# Gripper_Control_Board.net
KiCad netlist of a schematic drawn in EAGLE
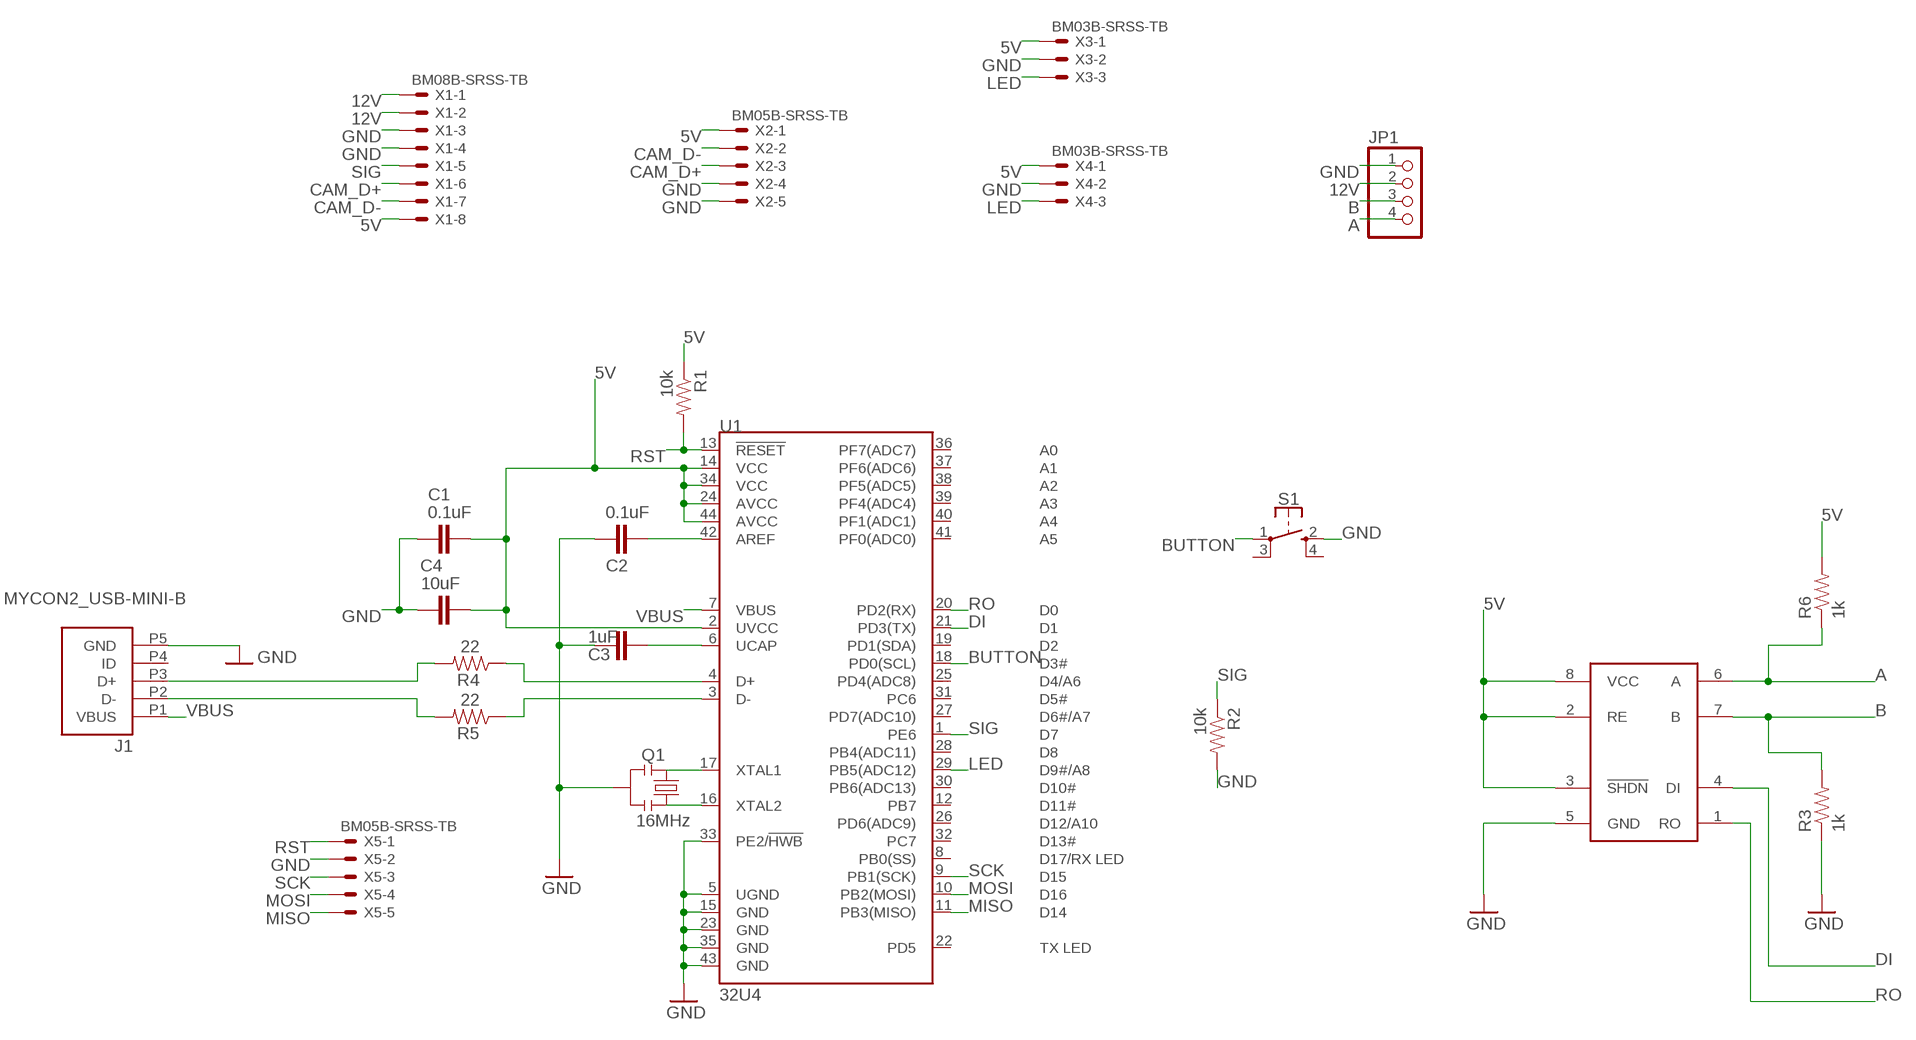
[diagram p0: schematic, sheet 1]

(export (version "E")
  (design (tool "Eeschema 10.0.6"))
  (components
    (comp (ref "C1")
      (value "0.1uF")
      (footprint "eagle-import:0603-CAP")
      (libsource (lib "eagle-import") (part "CAP0603-CAP"))
    )
    (comp (ref "C2")
      (value "0.1uF")
      (footprint "eagle-import:0603-CAP")
      (libsource (lib "eagle-import") (part "CAP0603-CAP"))
    )
    (comp (ref "C3")
      (value "1uF")
      (footprint "eagle-import:0603-CAP")
      (libsource (lib "eagle-import") (part "CAP0603-CAP"))
    )
    (comp (ref "C4")
      (value "10uF")
      (footprint "eagle-import:0805")
      (libsource (lib "eagle-import") (part "CAP0805"))
    )
    (comp (ref "J1")
      (value "MYCON2_USB-MINI-B")
      (footprint "eagle-import:CON2_USB_MICRO_B_AT")
      (libsource (lib "eagle-import") (part "MYCON2_USB-MINI-B"))
    )
    (comp (ref "JP1")
      (value "PINHD-1X4")
      (footprint "eagle-import:1X04")
      (libsource (lib "eagle-import") (part "PINHD-1X4"))
    )
    (comp (ref "Q1")
      (value "16MHz")
      (footprint "eagle-import:RESONATOR-SMD")
      (libsource (lib "eagle-import") (part "RESONATORSMD"))
    )
    (comp (ref "R1")
      (value "10k")
      (footprint "eagle-import:0603-RES")
      (libsource (lib "eagle-import") (part "RESISTOR0603"))
    )
    (comp (ref "R2")
      (value "10k")
      (footprint "eagle-import:0603-RES")
      (libsource (lib "eagle-import") (part "RESISTOR0603"))
    )
    (comp (ref "R3")
      (value "1k")
      (footprint "eagle-import:0603-RES")
      (libsource (lib "eagle-import") (part "RESISTOR0603-RES"))
    )
    (comp (ref "R4")
      (value "22")
      (footprint "eagle-import:0603-RES")
      (fields (field (name "SPICEPREFIX") "R"))
      (libsource (lib "eagle-import") (part "RESISTOR0603"))
    )
    (comp (ref "R5")
      (value "22")
      (footprint "eagle-import:0603-RES")
      (libsource (lib "eagle-import") (part "RESISTOR0603"))
    )
    (comp (ref "R6")
      (value "1k")
      (footprint "eagle-import:0603-RES")
      (libsource (lib "eagle-import") (part "RESISTOR0603-RES"))
    )
    (comp (ref "S1")
      (value "SKSGAAE010")
      (footprint "eagle-import:SKSG")
      (fields (field (name "MOUSER_PART_NUMBER") "688-SKSGAAE010"))
      (libsource (lib "eagle-import") (part "SKSGAAE010"))
    )
    (comp (ref "U1")
      (value "32U4")
      (footprint "eagle-import:QFN-44-NOPAD")
      (libsource (lib "eagle-import") (part "ATMEGA32U4QFN2"))
    )
    (comp (ref "U2")
      (value "MAX13487")
      (footprint "eagle-import:MAX13487")
      (libsource (lib "eagle-import") (part "MAX13487SOIC"))
    )
    (comp (ref "X1")
      (value "BM08B-SRSS-TB")
      (footprint "eagle-import:BM08B-SRSS-TB")
      (libsource (lib "eagle-import") (part "?M08B-SRSS-TBB"))
    )
    (comp (ref "X2")
      (value "BM05B-SRSS-TB")
      (footprint "eagle-import:BM05B-SRSS-TB")
      (libsource (lib "eagle-import") (part "?M05B-SRSS-TBB"))
    )
    (comp (ref "X3")
      (value "BM03B-SRSS-TB")
      (footprint "eagle-import:BM03B-SRSS-TB")
      (libsource (lib "eagle-import") (part "?M03B-SRSS-TBB"))
    )
    (comp (ref "X4")
      (value "BM03B-SRSS-TB")
      (footprint "eagle-import:BM03B-SRSS-TB")
      (libsource (lib "eagle-import") (part "?M03B-SRSS-TBB"))
    )
    (comp (ref "X5")
      (value "BM05B-SRSS-TB")
      (footprint "eagle-import:BM05B-SRSS-TB")
      (libsource (lib "eagle-import") (part "?M05B-SRSS-TBB"))
    )
  )
  (nets
    (net (code "1") (name "/5V") (class "Default")
      (node (ref "C1") (pin "2") (pinfunction "2_2") (pintype "passive"))
      (node (ref "C4") (pin "2") (pinfunction "2_2") (pintype "passive"))
      (node (ref "R1") (pin "1") (pinfunction "1_1") (pintype "passive"))
      (node (ref "R6") (pin "2") (pinfunction "2_2") (pintype "passive"))
      (node (ref "U1") (pin "14") (pinfunction "VCC_14") (pintype "bidirectional"))
      (node (ref "U1") (pin "2") (pinfunction "UVCC_2") (pintype "bidirectional"))
      (node (ref "U1") (pin "24") (pinfunction "AVCC_24") (pintype "bidirectional"))
      (node (ref "U1") (pin "34") (pinfunction "VCC_34") (pintype "bidirectional"))
      (node (ref "U1") (pin "44") (pinfunction "AVCC_44") (pintype "bidirectional"))
      (node (ref "U2") (pin "2") (pinfunction "RE_2") (pintype "bidirectional"))
      (node (ref "U2") (pin "3") (pinfunction "~{SHDN}_3") (pintype "bidirectional"))
      (node (ref "U2") (pin "8") (pinfunction "VCC_8") (pintype "power_in"))
      (node (ref "X1") (pin "8") (pinfunction "S_8") (pintype "passive"))
      (node (ref "X2") (pin "1") (pinfunction "S_1") (pintype "passive"))
      (node (ref "X3") (pin "1") (pinfunction "S_1") (pintype "passive"))
      (node (ref "X4") (pin "1") (pinfunction "S_1") (pintype "passive"))
    )
    (net (code "2") (name "/12V") (class "Default")
      (node (ref "JP1") (pin "2") (pinfunction "2_2") (pintype "passive"))
      (node (ref "X1") (pin "1") (pinfunction "S_1") (pintype "passive"))
      (node (ref "X1") (pin "2") (pinfunction "S_2") (pintype "passive"))
    )
    (net (code "3") (name "/A") (class "Default")
      (node (ref "JP1") (pin "4") (pinfunction "4_4") (pintype "passive"))
      (node (ref "R6") (pin "1") (pinfunction "1_1") (pintype "passive"))
      (node (ref "U2") (pin "6") (pinfunction "A_6") (pintype "bidirectional"))
    )
    (net (code "4") (name "/B") (class "Default")
      (node (ref "JP1") (pin "3") (pinfunction "3_3") (pintype "passive"))
      (node (ref "R3") (pin "2") (pinfunction "2_2") (pintype "passive"))
      (node (ref "U2") (pin "7") (pinfunction "B_7") (pintype "bidirectional"))
    )
    (net (code "5") (name "/BUTTON") (class "Default")
      (node (ref "S1") (pin "1") (pinfunction "1_1") (pintype "passive"))
      (node (ref "U1") (pin "18") (pinfunction "PD0(SCL)_18") (pintype "bidirectional"))
    )
    (net (code "6") (name "/CAM_D+") (class "Default")
      (node (ref "X1") (pin "6") (pinfunction "S_6") (pintype "passive"))
      (node (ref "X2") (pin "3") (pinfunction "S_3") (pintype "passive"))
    )
    (net (code "7") (name "/CAM_D-") (class "Default")
      (node (ref "X1") (pin "7") (pinfunction "S_7") (pintype "passive"))
      (node (ref "X2") (pin "2") (pinfunction "S_2") (pintype "passive"))
    )
    (net (code "8") (name "/DI") (class "Default")
      (node (ref "U1") (pin "21") (pinfunction "PD3(TX)_21") (pintype "bidirectional"))
      (node (ref "U2") (pin "4") (pinfunction "DI_4") (pintype "input"))
    )
    (net (code "9") (name "/LED") (class "Default")
      (node (ref "U1") (pin "29") (pinfunction "PB5(ADC12)_29") (pintype "bidirectional"))
      (node (ref "X3") (pin "3") (pinfunction "S_3") (pintype "passive"))
      (node (ref "X4") (pin "3") (pinfunction "S_3") (pintype "passive"))
    )
    (net (code "10") (name "/MISO") (class "Default")
      (node (ref "U1") (pin "11") (pinfunction "PB3(MISO)_11") (pintype "bidirectional"))
      (node (ref "X5") (pin "5") (pinfunction "S_5") (pintype "passive"))
    )
    (net (code "11") (name "/MOSI") (class "Default")
      (node (ref "U1") (pin "10") (pinfunction "PB2(MOSI)_10") (pintype "bidirectional"))
      (node (ref "X5") (pin "4") (pinfunction "S_4") (pintype "passive"))
    )
    (net (code "12") (name "/RO") (class "Default")
      (node (ref "U1") (pin "20") (pinfunction "PD2(RX)_20") (pintype "bidirectional"))
      (node (ref "U2") (pin "1") (pinfunction "RO_1") (pintype "output"))
    )
    (net (code "13") (name "/RST") (class "Default")
      (node (ref "R1") (pin "2") (pinfunction "2_2") (pintype "passive"))
      (node (ref "U1") (pin "13") (pinfunction "~{RESET}_13") (pintype "bidirectional"))
      (node (ref "X5") (pin "1") (pinfunction "S_1") (pintype "passive"))
    )
    (net (code "14") (name "/SCK") (class "Default")
      (node (ref "U1") (pin "9") (pinfunction "PB1(SCK)_9") (pintype "bidirectional"))
      (node (ref "X5") (pin "3") (pinfunction "S_3") (pintype "passive"))
    )
    (net (code "15") (name "/SIG") (class "Default")
      (node (ref "R2") (pin "1") (pinfunction "1_1") (pintype "passive"))
      (node (ref "U1") (pin "1") (pinfunction "PE6_1") (pintype "bidirectional"))
      (node (ref "X1") (pin "5") (pinfunction "S_5") (pintype "passive"))
    )
    (net (code "16") (name "/VBUS") (class "Default")
      (node (ref "J1") (pin "P1") (pinfunction "VBUS_P1") (pintype "power_in"))
      (node (ref "U1") (pin "7") (pinfunction "VBUS_7") (pintype "bidirectional"))
    )
    (net (code "17") (name "GND") (class "Default")
      (node (ref "C1") (pin "1") (pinfunction "1_1") (pintype "passive"))
      (node (ref "C2") (pin "1") (pinfunction "1_1") (pintype "passive"))
      (node (ref "C3") (pin "1") (pinfunction "1_1") (pintype "passive"))
      (node (ref "C4") (pin "1") (pinfunction "1_1") (pintype "passive"))
      (node (ref "J1") (pin "P5") (pinfunction "GND_P5") (pintype "passive"))
      (node (ref "JP1") (pin "1") (pinfunction "1_1") (pintype "passive"))
      (node (ref "Q1") (pin "2") (pinfunction "2_2") (pintype "passive"))
      (node (ref "R2") (pin "2") (pinfunction "2_2") (pintype "passive"))
      (node (ref "R3") (pin "1") (pinfunction "1_1") (pintype "passive"))
      (node (ref "S1") (pin "2") (pinfunction "3_2") (pintype "passive"))
      (node (ref "U1") (pin "15") (pinfunction "GND_15") (pintype "bidirectional"))
      (node (ref "U1") (pin "23") (pinfunction "GND_23") (pintype "bidirectional"))
      (node (ref "U1") (pin "33") (pinfunction "PE2/~{HWB}_33") (pintype "bidirectional"))
      (node (ref "U1") (pin "35") (pinfunction "GND_35") (pintype "bidirectional"))
      (node (ref "U1") (pin "43") (pinfunction "GND_43") (pintype "bidirectional"))
      (node (ref "U1") (pin "5") (pinfunction "UGND_5") (pintype "bidirectional"))
      (node (ref "U2") (pin "5") (pinfunction "GND_5") (pintype "power_in"))
      (node (ref "X1") (pin "3") (pinfunction "S_3") (pintype "passive"))
      (node (ref "X1") (pin "4") (pinfunction "S_4") (pintype "passive"))
      (node (ref "X2") (pin "4") (pinfunction "S_4") (pintype "passive"))
      (node (ref "X2") (pin "5") (pinfunction "S_5") (pintype "passive"))
      (node (ref "X3") (pin "2") (pinfunction "S_2") (pintype "passive"))
      (node (ref "X4") (pin "2") (pinfunction "S_2") (pintype "passive"))
      (node (ref "X5") (pin "2") (pinfunction "S_2") (pintype "passive"))
    )
    (net (code "18") (name "Net-(J1-D+)") (class "Default")
      (node (ref "J1") (pin "P3") (pinfunction "D+_P3") (pintype "bidirectional"))
      (node (ref "R4") (pin "2") (pinfunction "2_2") (pintype "passive"))
    )
    (net (code "19") (name "Net-(J1-D-)") (class "Default")
      (node (ref "J1") (pin "P2") (pinfunction "D-_P2") (pintype "bidirectional"))
      (node (ref "R5") (pin "2") (pinfunction "2_2") (pintype "passive"))
    )
    (net (code "20") (name "Net-(U1-AREF)") (class "Default")
      (node (ref "C2") (pin "2") (pinfunction "2_2") (pintype "passive"))
      (node (ref "U1") (pin "42") (pinfunction "AREF_42") (pintype "bidirectional"))
    )
    (net (code "21") (name "Net-(U1-D+)") (class "Default")
      (node (ref "R4") (pin "1") (pinfunction "1_1") (pintype "passive"))
      (node (ref "U1") (pin "4") (pinfunction "D+_4") (pintype "bidirectional"))
    )
    (net (code "22") (name "Net-(U1-D-)") (class "Default")
      (node (ref "R5") (pin "1") (pinfunction "1_1") (pintype "passive"))
      (node (ref "U1") (pin "3") (pinfunction "D-_3") (pintype "bidirectional"))
    )
    (net (code "23") (name "Net-(U1-UCAP)") (class "Default")
      (node (ref "C3") (pin "2") (pinfunction "2_2") (pintype "passive"))
      (node (ref "U1") (pin "6") (pinfunction "UCAP_6") (pintype "bidirectional"))
    )
    (net (code "24") (name "Net-(U1-XTAL1)") (class "Default")
      (node (ref "Q1") (pin "1") (pinfunction "1_1") (pintype "passive"))
      (node (ref "U1") (pin "17") (pinfunction "XTAL1_17") (pintype "bidirectional"))
    )
    (net (code "25") (name "Net-(U1-XTAL2)") (class "Default")
      (node (ref "Q1") (pin "3") (pinfunction "3_3") (pintype "passive"))
      (node (ref "U1") (pin "16") (pinfunction "XTAL2_16") (pintype "bidirectional"))
    )
    (net (code "26") (name "unconnected-(J1-ID-PadP4)") (class "Default")
      (node (ref "J1") (pin "P4") (pinfunction "ID_P4") (pintype "bidirectional"))
    )
    (net (code "27") (name "unconnected-(S1-2-Pad3)") (class "Default")
      (node (ref "S1") (pin "3") (pinfunction "2_3") (pintype "passive"))
    )
    (net (code "28") (name "unconnected-(S1-Pad4)") (class "Default")
      (node (ref "S1") (pin "4") (pinfunction "4_4") (pintype "passive"))
    )
    (net (code "29") (name "unconnected-(U1-PB0(SS)-Pad8)") (class "Default")
      (node (ref "U1") (pin "8") (pinfunction "PB0(SS)_8") (pintype "bidirectional"))
    )
    (net (code "30") (name "unconnected-(U1-PB4(ADC11)-Pad28)") (class "Default")
      (node (ref "U1") (pin "28") (pinfunction "PB4(ADC11)_28") (pintype "bidirectional"))
    )
    (net (code "31") (name "unconnected-(U1-PB6(ADC13)-Pad30)") (class "Default")
      (node (ref "U1") (pin "30") (pinfunction "PB6(ADC13)_30") (pintype "bidirectional"))
    )
    (net (code "32") (name "unconnected-(U1-PB7-Pad12)") (class "Default")
      (node (ref "U1") (pin "12") (pinfunction "PB7_12") (pintype "bidirectional"))
    )
    (net (code "33") (name "unconnected-(U1-PC6-Pad31)") (class "Default")
      (node (ref "U1") (pin "31") (pinfunction "PC6_31") (pintype "bidirectional"))
    )
    (net (code "34") (name "unconnected-(U1-PC7-Pad32)") (class "Default")
      (node (ref "U1") (pin "32") (pinfunction "PC7_32") (pintype "bidirectional"))
    )
    (net (code "35") (name "unconnected-(U1-PD1(SDA)-Pad19)") (class "Default")
      (node (ref "U1") (pin "19") (pinfunction "PD1(SDA)_19") (pintype "bidirectional"))
    )
    (net (code "36") (name "unconnected-(U1-PD4(ADC8)-Pad25)") (class "Default")
      (node (ref "U1") (pin "25") (pinfunction "PD4(ADC8)_25") (pintype "bidirectional"))
    )
    (net (code "37") (name "unconnected-(U1-PD5-Pad22)") (class "Default")
      (node (ref "U1") (pin "22") (pinfunction "PD5_22") (pintype "bidirectional"))
    )
    (net (code "38") (name "unconnected-(U1-PD6(ADC9)-Pad26)") (class "Default")
      (node (ref "U1") (pin "26") (pinfunction "PD6(ADC9)_26") (pintype "bidirectional"))
    )
    (net (code "39") (name "unconnected-(U1-PD7(ADC10)-Pad27)") (class "Default")
      (node (ref "U1") (pin "27") (pinfunction "PD7(ADC10)_27") (pintype "bidirectional"))
    )
    (net (code "40") (name "unconnected-(U1-PF0(ADC0)-Pad41)") (class "Default")
      (node (ref "U1") (pin "41") (pinfunction "PF0(ADC0)_41") (pintype "bidirectional"))
    )
    (net (code "41") (name "unconnected-(U1-PF1(ADC1)-Pad40)") (class "Default")
      (node (ref "U1") (pin "40") (pinfunction "PF1(ADC1)_40") (pintype "bidirectional"))
    )
    (net (code "42") (name "unconnected-(U1-PF4(ADC4)-Pad39)") (class "Default")
      (node (ref "U1") (pin "39") (pinfunction "PF4(ADC4)_39") (pintype "bidirectional"))
    )
    (net (code "43") (name "unconnected-(U1-PF5(ADC5)-Pad38)") (class "Default")
      (node (ref "U1") (pin "38") (pinfunction "PF5(ADC5)_38") (pintype "bidirectional"))
    )
    (net (code "44") (name "unconnected-(U1-PF6(ADC6)-Pad37)") (class "Default")
      (node (ref "U1") (pin "37") (pinfunction "PF6(ADC6)_37") (pintype "bidirectional"))
    )
    (net (code "45") (name "unconnected-(U1-PF7(ADC7)-Pad36)") (class "Default")
      (node (ref "U1") (pin "36") (pinfunction "PF7(ADC7)_36") (pintype "bidirectional"))
    )
  )
)
